# in-amp.net
KiCad netlist of a schematic drawn in Altium Designer
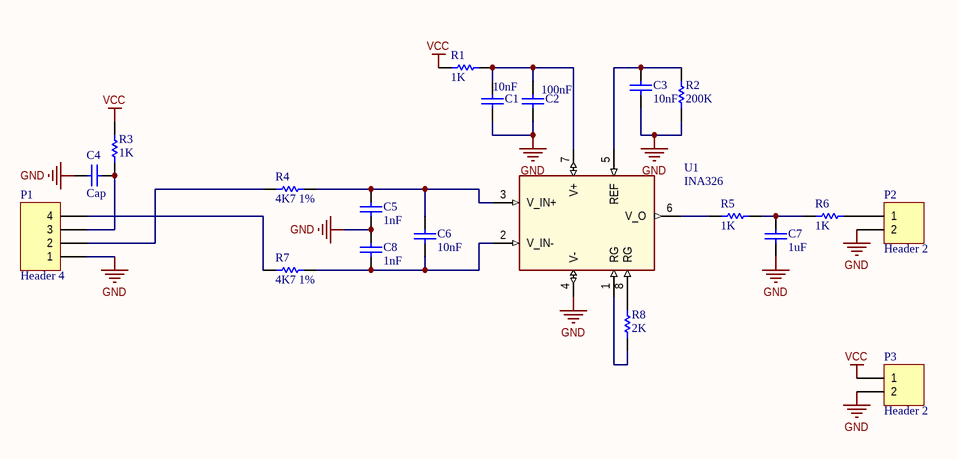
[diagram p0: in-amp.SchDoc]

(export (version "E")
  (design (tool "Eeschema 10.0.6"))
  (components
    (comp (ref "C1")
      (value "10nF")
      (footprint "6-0805_L")
      (description "Capacitor")
      (fields (field (name "PUBLISHER") "Altium Limited"))
      (libsource (lib "Miscellaneous Devices") (part "Cap"))
    )
    (comp (ref "C2")
      (value "100nF")
      (footprint "6-0805_L")
      (description "Capacitor")
      (fields (field (name "PUBLISHER") "Altium Limited"))
      (libsource (lib "Miscellaneous Devices") (part "Cap"))
    )
    (comp (ref "C3")
      (value "10nF")
      (footprint "6-0805_L")
      (description "Capacitor")
      (fields (field (name "PUBLISHER") "Altium Limited"))
      (libsource (lib "Miscellaneous Devices") (part "Cap"))
    )
    (comp (ref "C4")
      (value "Cap")
      (footprint "6-0805_L")
      (description "Capacitor")
      (fields (field (name "PUBLISHER") "Altium Limited"))
      (libsource (lib "Miscellaneous Devices") (part "Cap"))
    )
    (comp (ref "C5")
      (value "1nF")
      (footprint "6-0805_L")
      (description "Capacitor")
      (fields (field (name "PUBLISHER") "Altium Limited"))
      (libsource (lib "Miscellaneous Devices") (part "Cap"))
    )
    (comp (ref "C6")
      (value "10nF")
      (footprint "6-0805_L")
      (description "Capacitor")
      (fields (field (name "PUBLISHER") "Altium Limited"))
      (libsource (lib "Miscellaneous Devices") (part "Cap"))
    )
    (comp (ref "C7")
      (value "1uF")
      (footprint "6-0805_L")
      (description "Capacitor")
      (fields (field (name "PUBLISHER") "Altium Limited"))
      (libsource (lib "Miscellaneous Devices") (part "Cap"))
    )
    (comp (ref "C8")
      (value "1nF")
      (footprint "6-0805_L")
      (description "Capacitor")
      (fields (field (name "PUBLISHER") "Altium Limited"))
      (libsource (lib "Miscellaneous Devices") (part "Cap"))
    )
    (comp (ref "P1")
      (value "Header 4")
      (footprint "HDR1X4")
      (description "Header, 4-Pin")
      (fields (field (name "PUBLISHER") "Altium Limited"))
      (libsource (lib "Miscellaneous Connectors") (part "Header 4"))
    )
    (comp (ref "P2")
      (value "Header 2")
      (footprint "HDR1X2")
      (description "Header, 2-Pin")
      (fields (field (name "PUBLISHER") "Altium Limited"))
      (libsource (lib "Miscellaneous Connectors") (part "Header 2"))
    )
    (comp (ref "P3")
      (value "Header 2")
      (footprint "HDR1X2")
      (description "Header, 2-Pin")
      (fields (field (name "PUBLISHER") "Altium Limited"))
      (libsource (lib "Miscellaneous Connectors") (part "Header 2"))
    )
    (comp (ref "R1")
      (value "1K")
      (footprint "1210")
      (description "Resistor")
      (fields (field (name "PUBLISHER") "Altium Limited"))
      (libsource (lib "Miscellaneous Devices") (part "Res1"))
    )
    (comp (ref "R2")
      (value "200K")
      (footprint "6-0805_L")
      (description "Resistor")
      (fields (field (name "PUBLISHER") "Altium Limited"))
      (libsource (lib "Miscellaneous Devices") (part "Res1"))
    )
    (comp (ref "R3")
      (value "1K")
      (footprint "1210")
      (description "Resistor")
      (fields (field (name "PUBLISHER") "Altium Limited"))
      (libsource (lib "Miscellaneous Devices") (part "Res1"))
    )
    (comp (ref "R4")
      (value "4K7 1%")
      (footprint "6-0805_L")
      (description "Resistor")
      (fields (field (name "PUBLISHER") "Altium Limited"))
      (libsource (lib "Miscellaneous Devices") (part "Res1"))
    )
    (comp (ref "R5")
      (value "1K")
      (footprint "6-0805_L")
      (description "Resistor")
      (fields (field (name "PUBLISHER") "Altium Limited"))
      (libsource (lib "Miscellaneous Devices") (part "Res1"))
    )
    (comp (ref "R6")
      (value "1K")
      (footprint "6-0805_L")
      (description "Resistor")
      (fields (field (name "PUBLISHER") "Altium Limited"))
      (libsource (lib "Miscellaneous Devices") (part "Res1"))
    )
    (comp (ref "R7")
      (value "4K7 1%")
      (footprint "6-0805_L")
      (description "Resistor")
      (fields (field (name "PUBLISHER") "Altium Limited"))
      (libsource (lib "Miscellaneous Devices") (part "Res1"))
    )
    (comp (ref "R8")
      (value "2K")
      (footprint "6-0805_L")
      (description "Resistor")
      (fields (field (name "PUBLISHER") "Altium Limited"))
      (libsource (lib "Miscellaneous Devices") (part "Res1"))
    )
    (comp (ref "U1")
      (value "INA326")
      (footprint "MSOP8")
      (description "in-amp")
      (libsource (lib "DEVELER_Library") (part "INA326"))
    )
  )
  (nets
    (net (code "1") (name "GND") (class "Default")
      (node (ref "C1") (pin "1") (pinfunction "1_1") (pintype "passive"))
      (node (ref "C2") (pin "1") (pinfunction "1_1") (pintype "passive"))
      (node (ref "C3") (pin "1") (pinfunction "1_1") (pintype "passive"))
      (node (ref "C4") (pin "2") (pinfunction "2_2") (pintype "passive"))
      (node (ref "C5") (pin "1") (pinfunction "1_1") (pintype "passive"))
      (node (ref "C7") (pin "1") (pinfunction "1_1") (pintype "passive"))
      (node (ref "C8") (pin "2") (pinfunction "2_2") (pintype "passive"))
      (node (ref "P1") (pin "1") (pinfunction "1_1") (pintype "passive"))
      (node (ref "P2") (pin "2") (pinfunction "2_2") (pintype "passive"))
      (node (ref "P3") (pin "2") (pinfunction "2_2") (pintype "passive"))
      (node (ref "R2") (pin "2") (pinfunction "2_2") (pintype "passive"))
      (node (ref "U1") (pin "4") (pinfunction "V-_4") (pintype "bidirectional"))
    )
    (net (code "2") (name "Net-(C4-Pad1)") (class "Default")
      (node (ref "C4") (pin "1") (pinfunction "1_1") (pintype "passive"))
      (node (ref "P1") (pin "3") (pinfunction "3_3") (pintype "passive"))
      (node (ref "R3") (pin "1") (pinfunction "1_1") (pintype "passive"))
    )
    (net (code "3") (name "Net-(C7-Pad2)") (class "Default")
      (node (ref "C7") (pin "2") (pinfunction "2_2") (pintype "passive"))
      (node (ref "R5") (pin "1") (pinfunction "1_1") (pintype "passive"))
      (node (ref "R6") (pin "2") (pinfunction "2_2") (pintype "passive"))
    )
    (net (code "4") (name "Net-(P1-Pad2)") (class "Default")
      (node (ref "P1") (pin "2") (pinfunction "2_2") (pintype "passive"))
      (node (ref "R4") (pin "2") (pinfunction "2_2") (pintype "passive"))
    )
    (net (code "5") (name "Net-(P1-Pad4)") (class "Default")
      (node (ref "P1") (pin "4") (pinfunction "4_4") (pintype "passive"))
      (node (ref "R7") (pin "2") (pinfunction "2_2") (pintype "passive"))
    )
    (net (code "6") (name "Net-(P2-Pad1)") (class "Default")
      (node (ref "P2") (pin "1") (pinfunction "1_1") (pintype "passive"))
      (node (ref "R6") (pin "1") (pinfunction "1_1") (pintype "passive"))
    )
    (net (code "7") (name "Net-(R8-Pad1)") (class "Default")
      (node (ref "R8") (pin "1") (pinfunction "1_1") (pintype "passive"))
      (node (ref "U1") (pin "1") (pinfunction "RG_1") (pintype "input"))
    )
    (net (code "8") (name "Net-(R8-Pad2)") (class "Default")
      (node (ref "R8") (pin "2") (pinfunction "2_2") (pintype "passive"))
      (node (ref "U1") (pin "8") (pinfunction "RG_8") (pintype "input"))
    )
    (net (code "9") (name "Net-(U1-REF)") (class "Default")
      (node (ref "C3") (pin "2") (pinfunction "2_2") (pintype "passive"))
      (node (ref "R2") (pin "1") (pinfunction "1_1") (pintype "passive"))
      (node (ref "U1") (pin "5") (pinfunction "REF_5") (pintype "input"))
    )
    (net (code "10") (name "Net-(U1-V+)") (class "Default")
      (node (ref "C1") (pin "2") (pinfunction "2_2") (pintype "passive"))
      (node (ref "C2") (pin "2") (pinfunction "2_2") (pintype "passive"))
      (node (ref "R1") (pin "2") (pinfunction "2_2") (pintype "passive"))
      (node (ref "U1") (pin "7") (pinfunction "V+_7") (pintype "bidirectional"))
    )
    (net (code "11") (name "Net-(U1-V_IN+)") (class "Default")
      (node (ref "C5") (pin "2") (pinfunction "2_2") (pintype "passive"))
      (node (ref "C6") (pin "2") (pinfunction "2_2") (pintype "passive"))
      (node (ref "R4") (pin "1") (pinfunction "1_1") (pintype "passive"))
      (node (ref "U1") (pin "3") (pinfunction "V_IN+_3") (pintype "input"))
    )
    (net (code "12") (name "Net-(U1-V_IN-)") (class "Default")
      (node (ref "C6") (pin "1") (pinfunction "1_1") (pintype "passive"))
      (node (ref "C8") (pin "1") (pinfunction "1_1") (pintype "passive"))
      (node (ref "R7") (pin "1") (pinfunction "1_1") (pintype "passive"))
      (node (ref "U1") (pin "2") (pinfunction "V_IN-_2") (pintype "input"))
    )
    (net (code "13") (name "Net-(U1-V_O)") (class "Default")
      (node (ref "R5") (pin "2") (pinfunction "2_2") (pintype "passive"))
      (node (ref "U1") (pin "6") (pinfunction "V_O_6") (pintype "output"))
    )
    (net (code "14") (name "VCC") (class "Default")
      (node (ref "P3") (pin "1") (pinfunction "1_1") (pintype "passive"))
      (node (ref "R1") (pin "1") (pinfunction "1_1") (pintype "passive"))
      (node (ref "R3") (pin "2") (pinfunction "2_2") (pintype "passive"))
    )
  )
)
